# MCU.net
KiCad netlist of a schematic drawn in Altium Designer
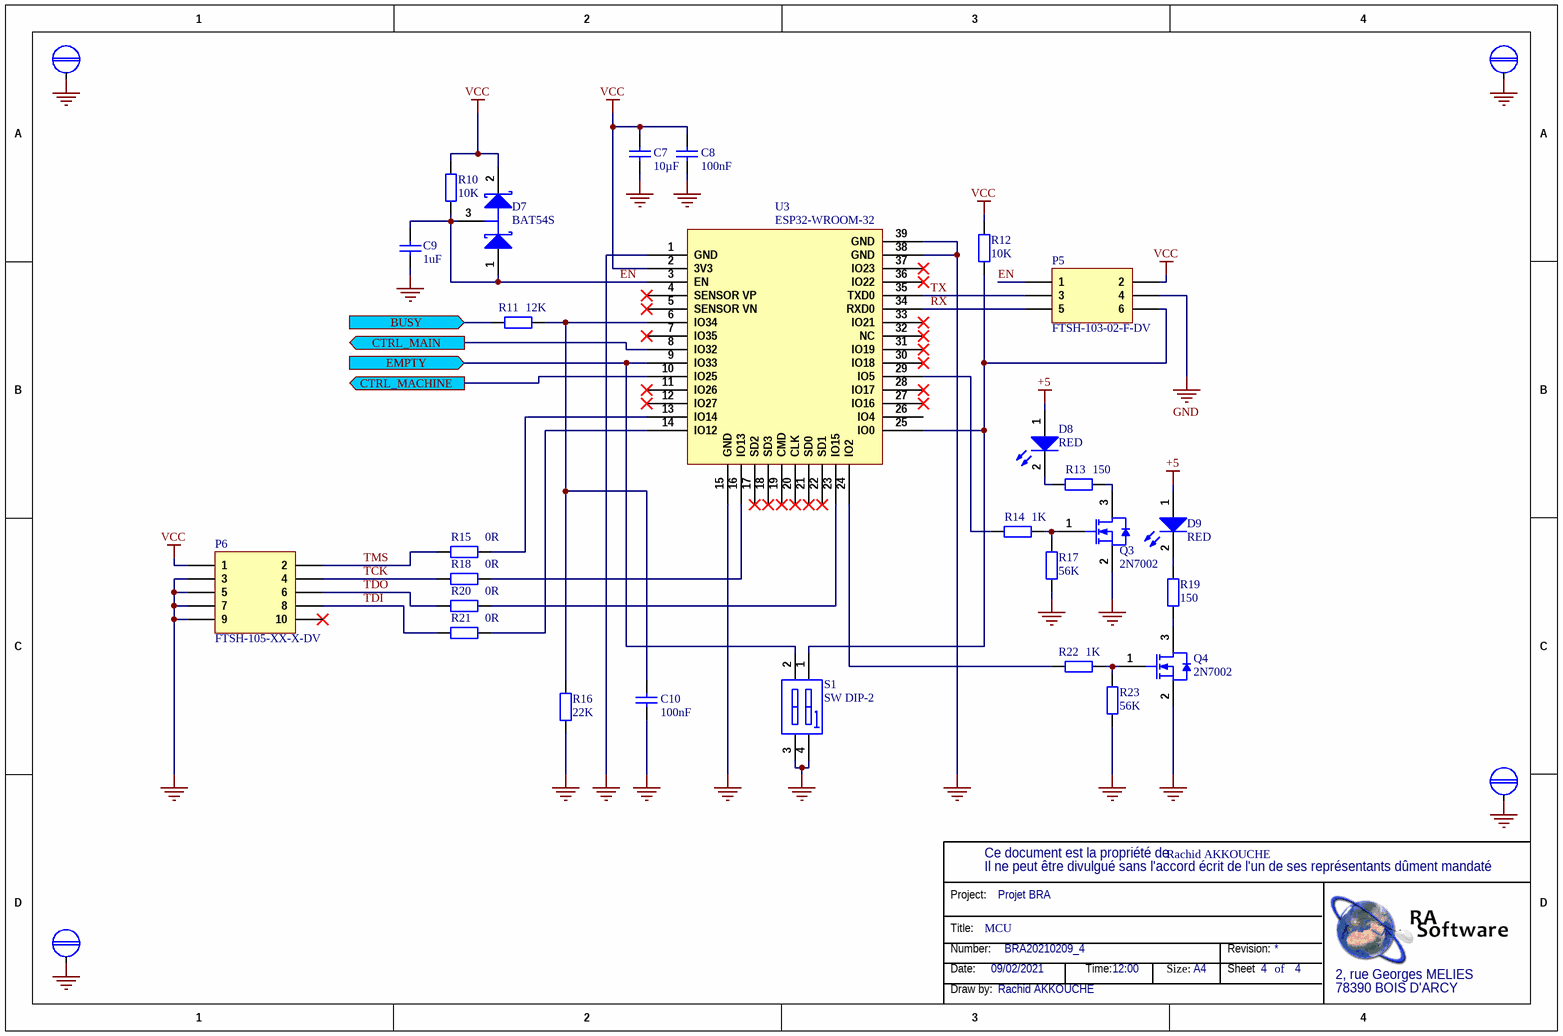
[diagram p0: MCU.SchDoc]

(export (version "E")
  (design (tool "Eeschema 10.0.6"))
  (components
    (comp (ref "C7")
      (value "10µF")
      (footprint "C 0805(2012)x0.65")
      (description "Capacitor non polarized 10µF SMD 0805")
      (fields (field (name "TOLERANCE") "10%") (field (name "VOLTAGE") "16V"))
      (libsource (lib "BRA") (part "Cap 0805 10uF"))
    )
    (comp (ref "C8")
      (value "100nF")
      (footprint "C 0805(2012)x0.65")
      (description "Capacitor")
      (fields
        (field (name "MANUFACTURER") "MULTICOMP")
        (field (name "MANUFACTURER PART NUMBER") "MCCA000296")
      )
      (libsource (lib "BRA") (part "Cap 0805 100nF"))
    )
    (comp (ref "C9")
      (value "1uF")
      (footprint "C 0805(2012)x0.65")
      (description "Capacitor")
      (fields
        (field (name "MANUFACTURER") "MULTICOMP")
        (field (name "MANUFACTURER PART NUMBER") "MCCA000549")
      )
      (libsource (lib "BRA") (part "Cap 0805 1uF"))
    )
    (comp (ref "C10")
      (value "100nF")
      (footprint "C 0805(2012)x0.65")
      (description "Capacitor")
      (fields
        (field (name "MANUFACTURER") "MULTICOMP")
        (field (name "MANUFACTURER PART NUMBER") "MCCA000296")
      )
      (libsource (lib "BRA") (part "Cap 0805 100nF"))
    )
    (comp (ref "D7")
      (value "BAT54S")
      (footprint "SOT23")
      (description "Schottky Barrier Double Diode")
      (fields (field (name "MANUFACTURER") "MULTICOMP"))
      (libsource (lib "BRA") (part "BAT54S"))
    )
    (comp (ref "D8")
      (value "RED")
      (footprint "0603-LEDR")
      (description "Surface Mount Chip LED, Red")
      (fields
        (field (name "MANUFACTURER") "AVAGO TECHNOLOGIES")
        (field (name "MANUFACTURER PART NUMBER") "HSMH-C190.")
        (field (name "LONGUEUR/HAUTEUR") "1.6")
      )
      (libsource (lib "BRA") (part "HSMH-C190"))
    )
    (comp (ref "D9")
      (value "RED")
      (footprint "0603-LEDR")
      (description "Surface Mount Chip LED, Red")
      (fields
        (field (name "MANUFACTURER") "AVAGO TECHNOLOGIES")
        (field (name "MANUFACTURER PART NUMBER") "HSMH-C190.")
        (field (name "LONGUEUR/HAUTEUR") "1.6")
      )
      (libsource (lib "BRA") (part "HSMH-C190"))
    )
    (comp (ref "P5")
      (value "FTSH-103-02-F-DV")
      (footprint "SAMTEC_FTSH-103-02-F-DV")
      (description "Connector Header Surface Mount 6 position 0.050 (1.27mm)")
      (fields (field (name "MF") "Samtec"))
      (libsource (lib "BRA") (part "FTSH-103-02-F-DV"))
    )
    (comp (ref "P6")
      (value "FTSH-105-XX-X-DV")
      (footprint "SAMTEC_FTSH-105-XX-X-DV")
      (description "Connector Header Surface Mount 10 position 0.050 (1.27mm)")
      (fields (field (name "MF") "Samtec") (field (name "MP") "FTSH-105-01-L-DV"))
      (libsource (lib "BRA") (part "FTSH-105-XX-X-DV"))
    )
    (comp (ref "Q3")
      (value "2N7002")
      (footprint "SOT23")
      (description "N-channel Enhancement Mode Field-effect Transistor")
      (fields (field (name "MANUFACTURER") "FAIRCHILD SEMICONDUCTOR"))
      (libsource (lib "BRA") (part "2N7002"))
    )
    (comp (ref "Q4")
      (value "2N7002")
      (footprint "SOT23")
      (description "N-channel Enhancement Mode Field-effect Transistor")
      (fields (field (name "MANUFACTURER") "FAIRCHILD SEMICONDUCTOR"))
      (libsource (lib "BRA") (part "2N7002"))
    )
    (comp (ref "R10")
      (value "10K")
      (footprint "R 0805(2012)")
      (description "Resistor SMD 0805 10K")
      (fields
        (field (name "MANUFACTURER") "MULTICOMP")
        (field (name "MANUFACTURER PART NUMBER") "MC0.1W08051%10KFR")
      )
      (libsource (lib "BRA") (part "Resistor 0805 10K"))
    )
    (comp (ref "R11")
      (value "12K")
      (footprint "R 0805(2012)")
      (description "Resistor SMD 0805 12K")
      (fields
        (field (name "MANUFACTURER") "Royal Electronic Factory")
        (field (name "MANUFACTURER PART NUMBER") "0805S8J0123T5E")
      )
      (libsource (lib "BRA") (part "Resistor 0805 12K"))
    )
    (comp (ref "R12")
      (value "10K")
      (footprint "R 0805(2012)")
      (description "Resistor SMD 0805 10K")
      (fields
        (field (name "MANUFACTURER") "MULTICOMP")
        (field (name "MANUFACTURER PART NUMBER") "MC0.1W08051%10KFR")
      )
      (libsource (lib "BRA") (part "Resistor 0805 10K"))
    )
    (comp (ref "R13")
      (value "150")
      (footprint "R 0805(2012)")
      (description "Resistor SMD 0805 150")
      (fields
        (field (name "MANUFACTURER") "YAGEO")
        (field (name "MANUFACTURER PART NUMBER") "RC0805JR-07150KL")
      )
      (libsource (lib "BRA") (part "Resistor 0805 150"))
    )
    (comp (ref "R14")
      (value "1K")
      (footprint "R 0805(2012)")
      (description "Resistor SMD 0805 1K")
      (fields
        (field (name "MANUFACTURER") "MULTICOMP")
        (field (name "MANUFACTURER PART NUMBER") "MC0.1W08051%1KFR")
      )
      (libsource (lib "BRA") (part "Resistor 0805 1K"))
    )
    (comp (ref "R15")
      (value "0R")
      (footprint "R 0805(2012)")
      (description "Resistor or Jumper")
      (fields
        (field (name "MANUFACTURER") "MULTICOMP")
        (field (name "MANUFACTURER PART NUMBER") "MCMR08X000 PTL")
      )
      (libsource (lib "BRA") (part "Resistor 0805 0R"))
    )
    (comp (ref "R16")
      (value "22K")
      (footprint "R 0805(2012)")
      (description "Resistor SMD 0805 22K")
      (fields
        (field (name "MANUFACTURER") "Royal Electronic Factory")
        (field (name "MANUFACTURER PART NUMBER") "0805S8J0223T5E")
      )
      (libsource (lib "BRA") (part "Resistor 0805 22K"))
    )
    (comp (ref "R17")
      (value "56K")
      (footprint "R 0805(2012)")
      (description "Resistor")
      (fields
        (field (name "MANUFACTURER") "MULTICOMP")
        (field (name "MANUFACTURER PART NUMBER") "MC0.1W08051%56KFR")
      )
      (libsource (lib "BRA") (part "Resistor 0805 56K"))
    )
    (comp (ref "R18")
      (value "0R")
      (footprint "R 0805(2012)")
      (description "Resistor or Jumper")
      (fields
        (field (name "MANUFACTURER") "MULTICOMP")
        (field (name "MANUFACTURER PART NUMBER") "MCMR08X000 PTL")
      )
      (libsource (lib "BRA") (part "Resistor 0805 0R"))
    )
    (comp (ref "R19")
      (value "150")
      (footprint "R 0805(2012)")
      (description "Resistor SMD 0805 150")
      (fields
        (field (name "MANUFACTURER") "YAGEO")
        (field (name "MANUFACTURER PART NUMBER") "RC0805JR-07150KL")
      )
      (libsource (lib "") (part "Resistor 0805 150_1"))
    )
    (comp (ref "R20")
      (value "0R")
      (footprint "R 0805(2012)")
      (description "Resistor or Jumper")
      (fields
        (field (name "MANUFACTURER") "MULTICOMP")
        (field (name "MANUFACTURER PART NUMBER") "MCMR08X000 PTL")
      )
      (libsource (lib "BRA") (part "Resistor 0805 0R"))
    )
    (comp (ref "R21")
      (value "0R")
      (footprint "R 0805(2012)")
      (description "Resistor or Jumper")
      (fields
        (field (name "MANUFACTURER") "MULTICOMP")
        (field (name "MANUFACTURER PART NUMBER") "MCMR08X000 PTL")
      )
      (libsource (lib "BRA") (part "Resistor 0805 0R"))
    )
    (comp (ref "R22")
      (value "1K")
      (footprint "R 0805(2012)")
      (description "Resistor SMD 0805 1K")
      (fields
        (field (name "MANUFACTURER") "MULTICOMP")
        (field (name "MANUFACTURER PART NUMBER") "MC0.1W08051%1KFR")
      )
      (libsource (lib "BRA") (part "Resistor 0805 1K"))
    )
    (comp (ref "R23")
      (value "56K")
      (footprint "R 0805(2012)")
      (description "Resistor")
      (fields
        (field (name "MANUFACTURER") "MULTICOMP")
        (field (name "MANUFACTURER PART NUMBER") "MC0.1W08051%56KFR")
      )
      (libsource (lib "BRA") (part "Resistor 0805 56K"))
    )
    (comp (ref "S1")
      (value "SW DIP-2")
      (footprint "DIP SWITCH 2 POS")
      (description "DIP Switch, 2 Position, SPST")
      (fields (field (name "PUBLISHER") "Altium Limited"))
      (libsource (lib "Miscellaneous Devices") (part "SW DIP-2"))
    )
    (comp (ref "U3")
      (value "ESP32-WROOM-32")
      (footprint "ESP32-WROOM-32X")
      (libsource (lib "BRA") (part "ESP32-WROOM-32x"))
    )
    (comp (ref "V1") (value "VIS") (footprint "HOLE M4") (libsource (lib "BRA") (part "VIS")))
    (comp (ref "V2") (value "VIS") (footprint "HOLE M4") (libsource (lib "BRA") (part "VIS")))
    (comp (ref "V3") (value "VIS") (footprint "BRA:HOLE M4") (libsource (lib "BRA") (part "VIS")))
    (comp (ref "V4") (value "VIS") (footprint "HOLE M4") (libsource (lib "BRA") (part "VIS")))
  )
  (nets
    (net (code "1") (name "+5") (class "Default")
      (node (ref "D8") (pin "1") (pinfunction "A_1") (pintype "passive"))
      (node (ref "D9") (pin "1") (pinfunction "A_1") (pintype "passive"))
    )
    (net (code "2") (name "/BUSY") (class "Default")
      (node (ref "R11") (pin "2") (pinfunction "2_2") (pintype "passive"))
    )
    (net (code "3") (name "/CTRL_MACHINE") (class "Default")
      (node (ref "U3") (pin "10") (pinfunction "IO25_10") (pintype "passive"))
    )
    (net (code "4") (name "/CTRL_MAIN") (class "Default")
      (node (ref "U3") (pin "8") (pinfunction "IO32_8") (pintype "passive"))
    )
    (net (code "5") (name "/EMPTY") (class "Default")
      (node (ref "S1") (pin "2") (pinfunction "A2_2") (pintype "passive"))
      (node (ref "U3") (pin "9") (pinfunction "IO33_9") (pintype "passive"))
    )
    (net (code "6") (name "/EN") (class "Default")
      (node (ref "C9") (pin "1") (pinfunction "1_1") (pintype "passive"))
      (node (ref "D7") (pin "1") (pinfunction "A_1") (pintype "passive"))
      (node (ref "D7") (pin "3") (pinfunction "C_3") (pintype "passive"))
      (node (ref "P5") (pin "1") (pinfunction "1_1") (pintype "passive"))
      (node (ref "R10") (pin "1") (pinfunction "1_1") (pintype "passive"))
      (node (ref "U3") (pin "3") (pinfunction "EN_3") (pintype "passive"))
    )
    (net (code "7") (name "/RX") (class "Default")
      (node (ref "P5") (pin "5") (pinfunction "5_5") (pintype "passive"))
      (node (ref "U3") (pin "34") (pinfunction "RXD0_34") (pintype "passive"))
    )
    (net (code "8") (name "/TCK") (class "Default")
      (node (ref "P6") (pin "4") (pinfunction "4_4") (pintype "passive"))
      (node (ref "R18") (pin "2") (pinfunction "2_2") (pintype "passive"))
    )
    (net (code "9") (name "/TDI") (class "Default")
      (node (ref "P6") (pin "8") (pinfunction "8_8") (pintype "passive"))
      (node (ref "R21") (pin "2") (pinfunction "2_2") (pintype "passive"))
    )
    (net (code "10") (name "/TDO") (class "Default")
      (node (ref "P6") (pin "6") (pinfunction "6_6") (pintype "passive"))
      (node (ref "R20") (pin "2") (pinfunction "2_2") (pintype "passive"))
    )
    (net (code "11") (name "/TMS") (class "Default")
      (node (ref "P6") (pin "2") (pinfunction "2_2") (pintype "passive"))
      (node (ref "R15") (pin "2") (pinfunction "2_2") (pintype "passive"))
    )
    (net (code "12") (name "/TX") (class "Default")
      (node (ref "P5") (pin "3") (pinfunction "3_3") (pintype "passive"))
      (node (ref "U3") (pin "35") (pinfunction "TXD0_35") (pintype "passive"))
    )
    (net (code "13") (name "GND") (class "Default")
      (node (ref "C10") (pin "1") (pinfunction "1_1") (pintype "passive"))
      (node (ref "C7") (pin "2") (pinfunction "2_2") (pintype "passive"))
      (node (ref "C8") (pin "1") (pinfunction "1_1") (pintype "passive"))
      (node (ref "C9") (pin "2") (pinfunction "2_2") (pintype "passive"))
      (node (ref "P5") (pin "4") (pinfunction "4_4") (pintype "passive"))
      (node (ref "P6") (pin "3") (pinfunction "3_3") (pintype "passive"))
      (node (ref "P6") (pin "5") (pinfunction "5_5") (pintype "passive"))
      (node (ref "P6") (pin "7") (pinfunction "7_7") (pintype "passive"))
      (node (ref "P6") (pin "9") (pinfunction "9_9") (pintype "passive"))
      (node (ref "Q3") (pin "2") (pinfunction "S_2") (pintype "passive"))
      (node (ref "Q4") (pin "2") (pinfunction "S_2") (pintype "passive"))
      (node (ref "R16") (pin "2") (pinfunction "2_2") (pintype "passive"))
      (node (ref "R17") (pin "1") (pinfunction "1_1") (pintype "passive"))
      (node (ref "R23") (pin "1") (pinfunction "1_1") (pintype "passive"))
      (node (ref "S1") (pin "3") (pinfunction "B2_3") (pintype "passive"))
      (node (ref "S1") (pin "4") (pinfunction "B1_4") (pintype "passive"))
      (node (ref "U3") (pin "1") (pinfunction "GND_1") (pintype "passive"))
      (node (ref "U3") (pin "15") (pinfunction "GND_15") (pintype "passive"))
      (node (ref "U3") (pin "38") (pinfunction "GND_38") (pintype "passive"))
      (node (ref "U3") (pin "39") (pinfunction "GND_39") (pintype "power_in"))
      (node (ref "V1") (pin "1") (pinfunction "GND_1") (pintype "power_in"))
      (node (ref "V2") (pin "1") (pinfunction "GND_1") (pintype "power_in"))
      (node (ref "V3") (pin "1") (pinfunction "GND_1") (pintype "power_in"))
      (node (ref "V4") (pin "1") (pinfunction "GND_1") (pintype "power_in"))
    )
    (net (code "14") (name "Net-(D8-K)") (class "Default")
      (node (ref "D8") (pin "2") (pinfunction "K_2") (pintype "passive"))
      (node (ref "R13") (pin "2") (pinfunction "2_2") (pintype "passive"))
    )
    (net (code "15") (name "Net-(D9-K)") (class "Default")
      (node (ref "D9") (pin "2") (pinfunction "K_2") (pintype "passive"))
      (node (ref "R19") (pin "2") (pinfunction "2_2") (pintype "passive"))
    )
    (net (code "16") (name "Net-(Q3-D)") (class "Default")
      (node (ref "Q3") (pin "3") (pinfunction "D_3") (pintype "passive"))
      (node (ref "R13") (pin "1") (pinfunction "1_1") (pintype "passive"))
    )
    (net (code "17") (name "Net-(Q3-G)") (class "Default")
      (node (ref "Q3") (pin "1") (pinfunction "G_1") (pintype "passive"))
      (node (ref "R14") (pin "1") (pinfunction "1_1") (pintype "passive"))
      (node (ref "R17") (pin "2") (pinfunction "2_2") (pintype "passive"))
    )
    (net (code "18") (name "Net-(Q4-D)") (class "Default")
      (node (ref "Q4") (pin "3") (pinfunction "D_3") (pintype "passive"))
      (node (ref "R19") (pin "1") (pinfunction "1_1") (pintype "passive"))
    )
    (net (code "19") (name "Net-(Q4-G)") (class "Default")
      (node (ref "Q4") (pin "1") (pinfunction "G_1") (pintype "passive"))
      (node (ref "R22") (pin "1") (pinfunction "1_1") (pintype "passive"))
      (node (ref "R23") (pin "2") (pinfunction "2_2") (pintype "passive"))
    )
    (net (code "20") (name "Net-(S1-A1)") (class "Default")
      (node (ref "P5") (pin "6") (pinfunction "6_6") (pintype "passive"))
      (node (ref "R12") (pin "1") (pinfunction "1_1") (pintype "passive"))
      (node (ref "S1") (pin "1") (pinfunction "A1_1") (pintype "passive"))
      (node (ref "U3") (pin "25") (pinfunction "IO0_25") (pintype "passive"))
    )
    (net (code "21") (name "Net-(U3-IO2)") (class "Default")
      (node (ref "R22") (pin "2") (pinfunction "2_2") (pintype "passive"))
      (node (ref "U3") (pin "24") (pinfunction "IO2_24") (pintype "passive"))
    )
    (net (code "22") (name "Net-(U3-IO5)") (class "Default")
      (node (ref "R14") (pin "2") (pinfunction "2_2") (pintype "passive"))
      (node (ref "U3") (pin "29") (pinfunction "IO5_29") (pintype "passive"))
    )
    (net (code "23") (name "Net-(U3-IO12)") (class "Default")
      (node (ref "R21") (pin "1") (pinfunction "1_1") (pintype "passive"))
      (node (ref "U3") (pin "14") (pinfunction "IO12_14") (pintype "passive"))
    )
    (net (code "24") (name "Net-(U3-IO13)") (class "Default")
      (node (ref "R18") (pin "1") (pinfunction "1_1") (pintype "passive"))
      (node (ref "U3") (pin "16") (pinfunction "IO13_16") (pintype "passive"))
    )
    (net (code "25") (name "Net-(U3-IO14)") (class "Default")
      (node (ref "R15") (pin "1") (pinfunction "1_1") (pintype "passive"))
      (node (ref "U3") (pin "13") (pinfunction "IO14_13") (pintype "passive"))
    )
    (net (code "26") (name "Net-(U3-IO15)") (class "Default")
      (node (ref "R20") (pin "1") (pinfunction "1_1") (pintype "passive"))
      (node (ref "U3") (pin "23") (pinfunction "IO15_23") (pintype "passive"))
    )
    (net (code "27") (name "Net-(U3-IO34)") (class "Default")
      (node (ref "C10") (pin "2") (pinfunction "2_2") (pintype "passive"))
      (node (ref "R11") (pin "1") (pinfunction "1_1") (pintype "passive"))
      (node (ref "R16") (pin "1") (pinfunction "1_1") (pintype "passive"))
      (node (ref "U3") (pin "6") (pinfunction "IO34_6") (pintype "passive"))
    )
    (net (code "28") (name "VCC") (class "Default")
      (node (ref "C7") (pin "1") (pinfunction "1_1") (pintype "passive"))
      (node (ref "C8") (pin "2") (pinfunction "2_2") (pintype "passive"))
      (node (ref "D7") (pin "2") (pinfunction "K_2") (pintype "passive"))
      (node (ref "P5") (pin "2") (pinfunction "2_2") (pintype "passive"))
      (node (ref "P6") (pin "1") (pinfunction "1_1") (pintype "passive"))
      (node (ref "R10") (pin "2") (pinfunction "2_2") (pintype "passive"))
      (node (ref "R12") (pin "2") (pinfunction "2_2") (pintype "passive"))
      (node (ref "U3") (pin "2") (pinfunction "3V3_2") (pintype "passive"))
    )
    (net (code "29") (name "unconnected-(P6-Pad10)") (class "Default")
      (node (ref "P6") (pin "10") (pinfunction "10_10") (pintype "passive+no_connect"))
    )
    (net (code "30") (name "unconnected-(U3-CLK-Pad20)") (class "Default")
      (node (ref "U3") (pin "20") (pinfunction "CLK_20") (pintype "passive+no_connect"))
    )
    (net (code "31") (name "unconnected-(U3-CMD-Pad19)") (class "Default")
      (node (ref "U3") (pin "19") (pinfunction "CMD_19") (pintype "passive+no_connect"))
    )
    (net (code "32") (name "unconnected-(U3-IO4-Pad26)") (class "Default")
      (node (ref "U3") (pin "26") (pinfunction "IO4_26") (pintype "passive"))
    )
    (net (code "33") (name "unconnected-(U3-IO16-Pad27)") (class "Default")
      (node (ref "U3") (pin "27") (pinfunction "IO16_27") (pintype "passive+no_connect"))
    )
    (net (code "34") (name "unconnected-(U3-IO17-Pad28)") (class "Default")
      (node (ref "U3") (pin "28") (pinfunction "IO17_28") (pintype "passive+no_connect"))
    )
    (net (code "35") (name "unconnected-(U3-IO18-Pad30)") (class "Default")
      (node (ref "U3") (pin "30") (pinfunction "IO18_30") (pintype "passive+no_connect"))
    )
    (net (code "36") (name "unconnected-(U3-IO19-Pad31)") (class "Default")
      (node (ref "U3") (pin "31") (pinfunction "IO19_31") (pintype "passive+no_connect"))
    )
    (net (code "37") (name "unconnected-(U3-IO21-Pad33)") (class "Default")
      (node (ref "U3") (pin "33") (pinfunction "IO21_33") (pintype "passive+no_connect"))
    )
    (net (code "38") (name "unconnected-(U3-IO22-Pad36)") (class "Default")
      (node (ref "U3") (pin "36") (pinfunction "IO22_36") (pintype "passive+no_connect"))
    )
    (net (code "39") (name "unconnected-(U3-IO23-Pad37)") (class "Default")
      (node (ref "U3") (pin "37") (pinfunction "IO23_37") (pintype "passive+no_connect"))
    )
    (net (code "40") (name "unconnected-(U3-IO26-Pad11)") (class "Default")
      (node (ref "U3") (pin "11") (pinfunction "IO26_11") (pintype "passive+no_connect"))
    )
    (net (code "41") (name "unconnected-(U3-IO27-Pad12)") (class "Default")
      (node (ref "U3") (pin "12") (pinfunction "IO27_12") (pintype "passive+no_connect"))
    )
    (net (code "42") (name "unconnected-(U3-IO35-Pad7)") (class "Default")
      (node (ref "U3") (pin "7") (pinfunction "IO35_7") (pintype "passive+no_connect"))
    )
    (net (code "43") (name "unconnected-(U3-NC-Pad32)") (class "Default")
      (node (ref "U3") (pin "32") (pinfunction "NC_32") (pintype "passive+no_connect"))
    )
    (net (code "44") (name "unconnected-(U3-SD0-Pad21)") (class "Default")
      (node (ref "U3") (pin "21") (pinfunction "SD0_21") (pintype "passive+no_connect"))
    )
    (net (code "45") (name "unconnected-(U3-SD1-Pad22)") (class "Default")
      (node (ref "U3") (pin "22") (pinfunction "SD1_22") (pintype "passive+no_connect"))
    )
    (net (code "46") (name "unconnected-(U3-SD2-Pad17)") (class "Default")
      (node (ref "U3") (pin "17") (pinfunction "SD2_17") (pintype "passive+no_connect"))
    )
    (net (code "47") (name "unconnected-(U3-SD3-Pad18)") (class "Default")
      (node (ref "U3") (pin "18") (pinfunction "SD3_18") (pintype "passive+no_connect"))
    )
    (net (code "48") (name "unconnected-(U3-SENSOR_VN-Pad5)") (class "Default")
      (node (ref "U3") (pin "5") (pinfunction "SENSOR_VN_5") (pintype "passive+no_connect"))
    )
    (net (code "49") (name "unconnected-(U3-SENSOR_VP-Pad4)") (class "Default")
      (node (ref "U3") (pin "4") (pinfunction "SENSOR_VP_4") (pintype "passive+no_connect"))
    )
  )
)
